# lcd_bias_v3_6.net
KiCad netlist of a schematic drawn in EAGLE
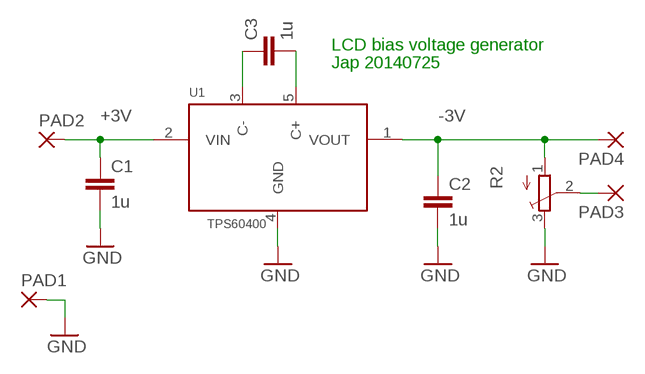
[diagram p0: schematic, sheet 1]

(export (version "E")
  (design (tool "Eeschema 10.0.6"))
  (components
    (comp (ref "C1")
      (value "1u")
      (footprint "eagle-import:C0603K")
      (libsource (lib "eagle-import") (part "C-EUC0603K"))
    )
    (comp (ref "C2")
      (value "1u")
      (footprint "eagle-import:C0603K")
      (libsource (lib "eagle-import") (part "C-EUC0603K"))
    )
    (comp (ref "C3")
      (value "1u")
      (footprint "eagle-import:C0603K")
      (libsource (lib "eagle-import") (part "C-EUC0603K"))
    )
    (comp (ref "PAD1")
      (value "1,6/0,8")
      (footprint "eagle-import:1,6_0,8")
      (libsource (lib "eagle-import") (part "1,6/0,8"))
    )
    (comp (ref "PAD2")
      (value "1,6/0,8")
      (footprint "eagle-import:1,6_0,8")
      (libsource (lib "eagle-import") (part "1,6/0,8"))
    )
    (comp (ref "PAD3")
      (value "1,6/0,8")
      (footprint "eagle-import:1,6_0,8")
      (libsource (lib "eagle-import") (part "1,6/0,8"))
    )
    (comp (ref "PAD4")
      (value "1,6/0,8")
      (footprint "eagle-import:1,6_0,8")
      (libsource (lib "eagle-import") (part "1,6/0,8"))
    )
    (comp (ref "R2")
      (value "TRIMMER3305")
      (footprint "eagle-import:RTRIM3305")
      (libsource (lib "eagle-import") (part "TRIMMER3305"))
    )
    (comp (ref "U1")
      (value "TPS60400")
      (footprint "eagle-import:SOT23-5")
      (libsource (lib "eagle-import") (part "TPS60400"))
    )
  )
  (nets
    (net (code "1") (name "/+3V") (class "Default")
      (node (ref "C1") (pin "1") (pinfunction "1_1") (pintype "passive"))
      (node (ref "PAD2") (pin "1") (pinfunction "P_1") (pintype "passive"))
      (node (ref "U1") (pin "2") (pinfunction "VIN_2") (pintype "bidirectional"))
    )
    (net (code "2") (name "/-3V") (class "Default")
      (node (ref "C2") (pin "1") (pinfunction "1_1") (pintype "passive"))
      (node (ref "PAD4") (pin "1") (pinfunction "P_1") (pintype "passive"))
      (node (ref "R2") (pin "1") (pinfunction "A_1") (pintype "passive"))
      (node (ref "U1") (pin "1") (pinfunction "VOUT_1") (pintype "bidirectional"))
    )
    (net (code "3") (name "GND") (class "Default")
      (node (ref "C1") (pin "2") (pinfunction "2_2") (pintype "passive"))
      (node (ref "C2") (pin "2") (pinfunction "2_2") (pintype "passive"))
      (node (ref "PAD1") (pin "1") (pinfunction "P_1") (pintype "passive"))
      (node (ref "R2") (pin "3") (pinfunction "E_3") (pintype "passive"))
      (node (ref "U1") (pin "4") (pinfunction "GND_4") (pintype "bidirectional"))
    )
    (net (code "4") (name "Net-(PAD3-P)") (class "Default")
      (node (ref "PAD3") (pin "1") (pinfunction "P_1") (pintype "passive"))
      (node (ref "R2") (pin "2") (pinfunction "S_2") (pintype "passive"))
    )
    (net (code "5") (name "Net-(U1-C+)") (class "Default")
      (node (ref "C3") (pin "2") (pinfunction "2_2") (pintype "passive"))
      (node (ref "U1") (pin "5") (pinfunction "C+_5") (pintype "bidirectional"))
    )
    (net (code "6") (name "Net-(U1-C-)") (class "Default")
      (node (ref "C3") (pin "1") (pinfunction "1_1") (pintype "passive"))
      (node (ref "U1") (pin "3") (pinfunction "C-_3") (pintype "bidirectional"))
    )
  )
)
